# LoRa_Photon2.net
KiCad netlist of a schematic drawn in EAGLE
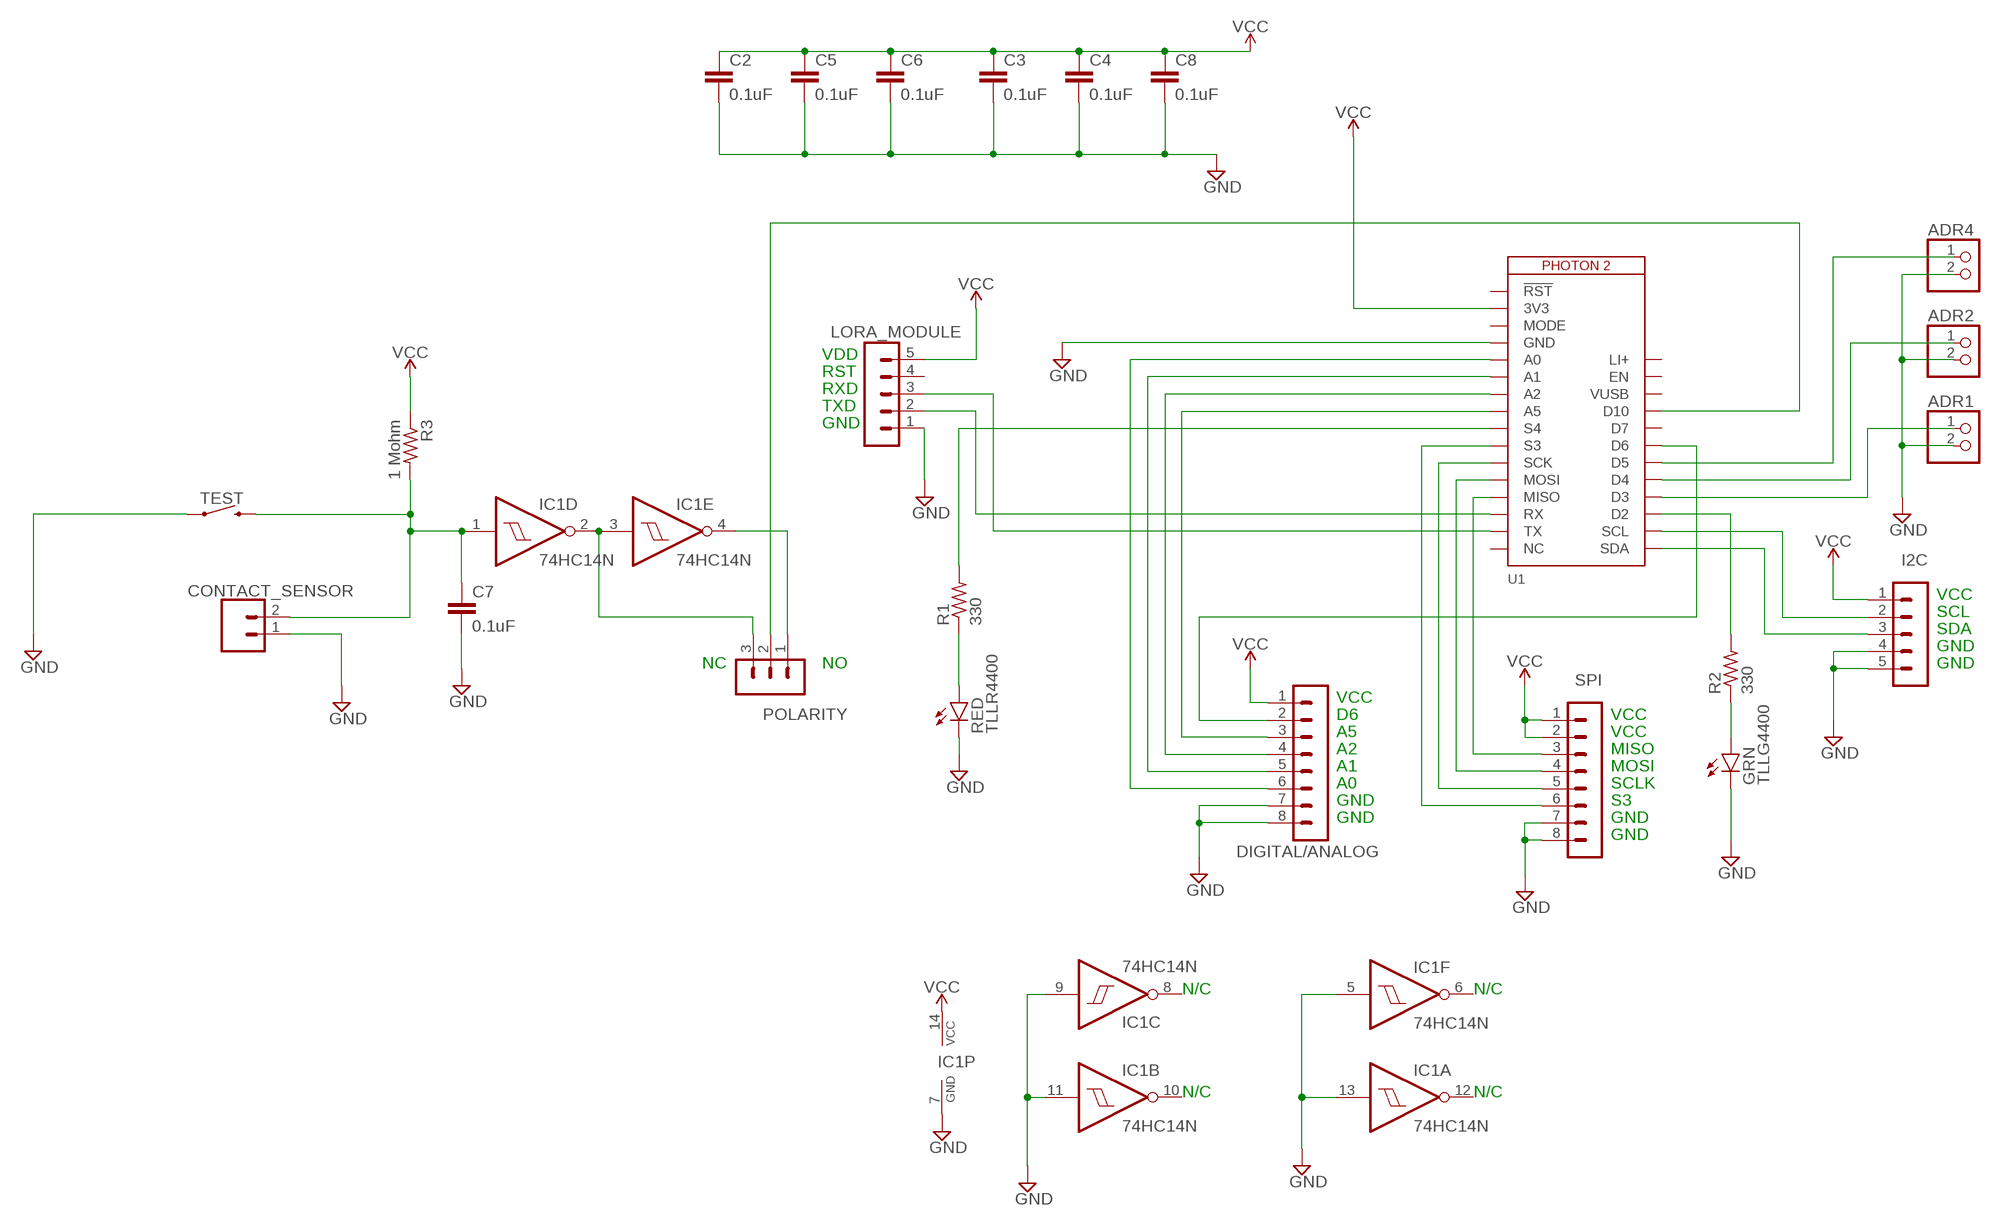
[diagram p0: schematic, sheet 2]

(export (version "E")
  (design (tool "Eeschema 10.0.6"))
  (components
    (comp (ref "ADR1")
      (value "PINHD-1X2")
      (footprint "eagle-import:1X02")
      (libsource (lib "eagle-import") (part "PINHD-1X2"))
    )
    (comp (ref "ADR2")
      (value "PINHD-1X2")
      (footprint "eagle-import:1X02")
      (libsource (lib "eagle-import") (part "PINHD-1X2"))
    )
    (comp (ref "ADR4")
      (value "PINHD-1X2")
      (footprint "eagle-import:1X02")
      (libsource (lib "eagle-import") (part "PINHD-1X2"))
    )
    (comp (ref "C2")
      (value "0.1uF")
      (footprint "eagle-import:CAP-PTH-SMALL-KIT")
      (libsource (lib "eagle-import") (part "0.1UF-KIT-EZ-50V-20%"))
    )
    (comp (ref "C3")
      (value "0.1uF")
      (footprint "eagle-import:CAP-PTH-SMALL-KIT")
      (libsource (lib "eagle-import") (part "0.1UF-KIT-EZ-50V-20%"))
    )
    (comp (ref "C4")
      (value "0.1uF")
      (footprint "eagle-import:CAP-PTH-SMALL-KIT")
      (libsource (lib "eagle-import") (part "0.1UF-KIT-EZ-50V-20%"))
    )
    (comp (ref "C5")
      (value "0.1uF")
      (footprint "eagle-import:CAP-PTH-SMALL-KIT")
      (libsource (lib "eagle-import") (part "0.1UF-KIT-EZ-50V-20%"))
    )
    (comp (ref "C6")
      (value "0.1uF")
      (footprint "eagle-import:CAP-PTH-SMALL-KIT")
      (libsource (lib "eagle-import") (part "0.1UF-KIT-EZ-50V-20%"))
    )
    (comp (ref "C7")
      (value "0.1uF")
      (footprint "eagle-import:CAP-PTH-SMALL-KIT")
      (libsource (lib "eagle-import") (part "0.1UF-KIT-EZ-50V-20%"))
    )
    (comp (ref "C8")
      (value "0.1uF")
      (footprint "eagle-import:CAP-PTH-SMALL-KIT")
      (libsource (lib "eagle-import") (part "0.1UF-KIT-EZ-50V-20%"))
    )
    (comp (ref "CONTACT_SENSOR")
      (value "CONN_023.5MM")
      (footprint "eagle-import:SCREWTERMINAL-3.5MM-2")
      (libsource (lib "eagle-import") (part "CONN_023.5MM"))
    )
    (comp (ref "DIGITAL/ANALOG")
      (value "MA08-1")
      (footprint "eagle-import:MA08-1")
      (libsource (lib "eagle-import") (part "MA08-1"))
    )
    (comp (ref "GRN")
      (value "TLLG4400")
      (footprint "eagle-import:LED3MM")
      (fields (field (name "MF") "VISHAY SEMICONDUCTOR"))
      (libsource (lib "eagle-import") (part "TLLG4400"))
    )
    (comp (ref "I2C")
      (value "MA05-1")
      (footprint "eagle-import:MA05-1")
      (libsource (lib "eagle-import") (part "MA05-1"))
    )
    (comp (ref "IC1")
      (value "74HC14N")
      (footprint "eagle-import:DIL14")
      (libsource (lib "eagle-import") (part "7414NHC"))
    )
    (comp (ref "LORA_MODULE")
      (value "MA05-1")
      (footprint "eagle-import:MA05-1")
      (libsource (lib "eagle-import") (part "MA05-1"))
    )
    (comp (ref "POLARITY")
      (value "MA03-1")
      (footprint "eagle-import:MA03-1")
      (libsource (lib "eagle-import") (part "MA03-1"))
    )
    (comp (ref "R1")
      (value "330")
      (footprint "eagle-import:0309_12")
      (libsource (lib "eagle-import") (part "R-US_0309/12"))
    )
    (comp (ref "R2")
      (value "330")
      (footprint "eagle-import:0309_12")
      (libsource (lib "eagle-import") (part "R-US_0309/12"))
    )
    (comp (ref "R3")
      (value "1 Mohm")
      (footprint "eagle-import:0309_12")
      (libsource (lib "eagle-import") (part "R-US_0309/12"))
    )
    (comp (ref "RED")
      (value "TLLR4400")
      (footprint "eagle-import:LED3MM")
      (fields (field (name "MF") "VISHAY SEMICONDUCTOR"))
      (libsource (lib "eagle-import") (part "TLLR4400"))
    )
    (comp (ref "SPI")
      (value "MA08-1")
      (footprint "eagle-import:MA08-1")
      (libsource (lib "eagle-import") (part "MA08-1"))
    )
    (comp (ref "TEST")
      (value "MOMENTARY-SWITCH-SPST-PTH-6.0MM")
      (footprint "eagle-import:TACTILE_SWITCH_PTH_6.0MM")
      (libsource (lib "eagle-import") (part "MOMENTARY-SWITCH-SPST-PTH-6.0MM"))
    )
    (comp (ref "U1")
      (value "PHOTON2")
      (footprint "eagle-import:PHOTON2")
      (libsource (lib "eagle-import") (part "PHOTON2"))
    )
  )
  (nets
    (net (code "1") (name "GND") (class "Default")
      (node (ref "ADR1") (pin "2") (pinfunction "2_2") (pintype "passive"))
      (node (ref "ADR2") (pin "2") (pinfunction "2_2") (pintype "passive"))
      (node (ref "ADR4") (pin "2") (pinfunction "2_2") (pintype "passive"))
      (node (ref "C2") (pin "2") (pinfunction "2_2") (pintype "passive"))
      (node (ref "C3") (pin "2") (pinfunction "2_2") (pintype "passive"))
      (node (ref "C4") (pin "2") (pinfunction "2_2") (pintype "passive"))
      (node (ref "C5") (pin "2") (pinfunction "2_2") (pintype "passive"))
      (node (ref "C6") (pin "2") (pinfunction "2_2") (pintype "passive"))
      (node (ref "C7") (pin "2") (pinfunction "2_2") (pintype "passive"))
      (node (ref "C8") (pin "2") (pinfunction "2_2") (pintype "passive"))
      (node (ref "CONTACT_SENSOR") (pin "1") (pinfunction "1_1") (pintype "passive"))
      (node (ref "DIGITAL/ANALOG") (pin "7") (pinfunction "7_7") (pintype "passive"))
      (node (ref "DIGITAL/ANALOG") (pin "8") (pinfunction "8_8") (pintype "passive"))
      (node (ref "GRN") (pin "K") (pinfunction "C_K") (pintype "passive"))
      (node (ref "I2C") (pin "4") (pinfunction "4_4") (pintype "passive"))
      (node (ref "I2C") (pin "5") (pinfunction "5_5") (pintype "passive"))
      (node (ref "IC1") (pin "11") (pinfunction "I_11") (pintype "input"))
      (node (ref "IC1") (pin "13") (pinfunction "I_13") (pintype "input"))
      (node (ref "IC1") (pin "5") (pinfunction "I_5") (pintype "input"))
      (node (ref "IC1") (pin "7") (pinfunction "GND_7") (pintype "power_in"))
      (node (ref "IC1") (pin "9") (pinfunction "I_9") (pintype "input"))
      (node (ref "LORA_MODULE") (pin "1") (pinfunction "1_1") (pintype "passive"))
      (node (ref "RED") (pin "K") (pinfunction "C_K") (pintype "passive"))
      (node (ref "SPI") (pin "7") (pinfunction "7_7") (pintype "passive"))
      (node (ref "SPI") (pin "8") (pinfunction "8_8") (pintype "passive"))
      (node (ref "TEST") (pin "1") (pinfunction "1_1") (pintype "passive"))
      (node (ref "U1") (pin "4") (pinfunction "GND_4") (pintype "power_in"))
    )
    (net (code "2") (name "LI+") (class "Default")
      (node (ref "U1") (pin "28") (pinfunction "LI+_28") (pintype "power_in"))
    )
    (net (code "3") (name "Net-(GRN-PadA)") (class "Default")
      (node (ref "GRN") (pin "A") (pinfunction "A_A") (pintype "passive"))
      (node (ref "R2") (pin "1") (pinfunction "1_1") (pintype "passive"))
    )
    (net (code "4") (name "Net-(IC1D-I)") (class "Default")
      (node (ref "C7") (pin "1") (pinfunction "1_1") (pintype "passive"))
      (node (ref "CONTACT_SENSOR") (pin "2") (pinfunction "2_2") (pintype "passive"))
      (node (ref "IC1") (pin "1") (pinfunction "I_1") (pintype "input"))
      (node (ref "R3") (pin "2") (pinfunction "2_2") (pintype "passive"))
      (node (ref "TEST") (pin "3") (pinfunction "2_3") (pintype "passive"))
    )
    (net (code "5") (name "Net-(IC1D-O)") (class "Default")
      (node (ref "IC1") (pin "2") (pinfunction "O_2") (pintype "output"))
      (node (ref "IC1") (pin "3") (pinfunction "I_3") (pintype "input"))
      (node (ref "POLARITY") (pin "3") (pinfunction "3_3") (pintype "passive"))
    )
    (net (code "6") (name "Net-(IC1E-O)") (class "Default")
      (node (ref "IC1") (pin "4") (pinfunction "O_4") (pintype "output"))
      (node (ref "POLARITY") (pin "1") (pinfunction "1_1") (pintype "passive"))
    )
    (net (code "7") (name "Net-(R1-Pad1)") (class "Default")
      (node (ref "R1") (pin "1") (pinfunction "1_1") (pintype "passive"))
      (node (ref "RED") (pin "A") (pinfunction "A_A") (pintype "passive"))
    )
    (net (code "8") (name "Net-(U1-A0)") (class "Default")
      (node (ref "DIGITAL/ANALOG") (pin "6") (pinfunction "6_6") (pintype "passive"))
      (node (ref "U1") (pin "5") (pinfunction "A0_5") (pintype "bidirectional"))
    )
    (net (code "9") (name "Net-(U1-A1)") (class "Default")
      (node (ref "DIGITAL/ANALOG") (pin "5") (pinfunction "5_5") (pintype "passive"))
      (node (ref "U1") (pin "6") (pinfunction "A1_6") (pintype "bidirectional"))
    )
    (net (code "10") (name "Net-(U1-A2)") (class "Default")
      (node (ref "DIGITAL/ANALOG") (pin "4") (pinfunction "4_4") (pintype "passive"))
      (node (ref "U1") (pin "7") (pinfunction "A2_7") (pintype "bidirectional"))
    )
    (net (code "11") (name "Net-(U1-A5)") (class "Default")
      (node (ref "DIGITAL/ANALOG") (pin "3") (pinfunction "3_3") (pintype "passive"))
      (node (ref "U1") (pin "8") (pinfunction "A5_8") (pintype "bidirectional"))
    )
    (net (code "12") (name "Net-(U1-D2)") (class "Default")
      (node (ref "R2") (pin "2") (pinfunction "2_2") (pintype "passive"))
      (node (ref "U1") (pin "19") (pinfunction "D2_19") (pintype "bidirectional"))
    )
    (net (code "13") (name "Net-(U1-D3)") (class "Default")
      (node (ref "ADR1") (pin "1") (pinfunction "1_1") (pintype "passive"))
      (node (ref "U1") (pin "20") (pinfunction "D3_20") (pintype "bidirectional"))
    )
    (net (code "14") (name "Net-(U1-D4)") (class "Default")
      (node (ref "ADR2") (pin "1") (pinfunction "1_1") (pintype "passive"))
      (node (ref "U1") (pin "21") (pinfunction "D4_21") (pintype "bidirectional"))
    )
    (net (code "15") (name "Net-(U1-D5)") (class "Default")
      (node (ref "ADR4") (pin "1") (pinfunction "1_1") (pintype "passive"))
      (node (ref "U1") (pin "22") (pinfunction "D5_22") (pintype "bidirectional"))
    )
    (net (code "16") (name "Net-(U1-D6)") (class "Default")
      (node (ref "DIGITAL/ANALOG") (pin "2") (pinfunction "2_2") (pintype "passive"))
      (node (ref "U1") (pin "23") (pinfunction "D6_23") (pintype "bidirectional"))
    )
    (net (code "17") (name "Net-(U1-D10)") (class "Default")
      (node (ref "POLARITY") (pin "2") (pinfunction "2_2") (pintype "passive"))
      (node (ref "U1") (pin "25") (pinfunction "D10_25") (pintype "bidirectional"))
    )
    (net (code "18") (name "Net-(U1-MISO)") (class "Default")
      (node (ref "SPI") (pin "3") (pinfunction "3_3") (pintype "passive"))
      (node (ref "U1") (pin "13") (pinfunction "MISO_13") (pintype "bidirectional"))
    )
    (net (code "19") (name "Net-(U1-MOSI)") (class "Default")
      (node (ref "SPI") (pin "4") (pinfunction "4_4") (pintype "passive"))
      (node (ref "U1") (pin "12") (pinfunction "MOSI_12") (pintype "bidirectional"))
    )
    (net (code "20") (name "Net-(U1-RX)") (class "Default")
      (node (ref "LORA_MODULE") (pin "2") (pinfunction "2_2") (pintype "passive"))
      (node (ref "U1") (pin "14") (pinfunction "RX_14") (pintype "bidirectional"))
    )
    (net (code "21") (name "Net-(U1-S3)") (class "Default")
      (node (ref "SPI") (pin "6") (pinfunction "6_6") (pintype "passive"))
      (node (ref "U1") (pin "10") (pinfunction "S3_10") (pintype "bidirectional"))
    )
    (net (code "22") (name "Net-(U1-S4)") (class "Default")
      (node (ref "R1") (pin "2") (pinfunction "2_2") (pintype "passive"))
      (node (ref "U1") (pin "9") (pinfunction "S4_9") (pintype "bidirectional"))
    )
    (net (code "23") (name "Net-(U1-SCK)") (class "Default")
      (node (ref "SPI") (pin "5") (pinfunction "5_5") (pintype "passive"))
      (node (ref "U1") (pin "11") (pinfunction "SCK_11") (pintype "bidirectional"))
    )
    (net (code "24") (name "Net-(U1-SCL)") (class "Default")
      (node (ref "I2C") (pin "2") (pinfunction "2_2") (pintype "passive"))
      (node (ref "U1") (pin "18") (pinfunction "SCL_18") (pintype "bidirectional"))
    )
    (net (code "25") (name "Net-(U1-SDA)") (class "Default")
      (node (ref "I2C") (pin "3") (pinfunction "3_3") (pintype "passive"))
      (node (ref "U1") (pin "17") (pinfunction "SDA_17") (pintype "bidirectional"))
    )
    (net (code "26") (name "Net-(U1-TX)") (class "Default")
      (node (ref "LORA_MODULE") (pin "3") (pinfunction "3_3") (pintype "passive"))
      (node (ref "U1") (pin "15") (pinfunction "TX_15") (pintype "bidirectional"))
    )
    (net (code "27") (name "VCC") (class "Default")
      (node (ref "C2") (pin "1") (pinfunction "1_1") (pintype "passive"))
      (node (ref "C3") (pin "1") (pinfunction "1_1") (pintype "passive"))
      (node (ref "C4") (pin "1") (pinfunction "1_1") (pintype "passive"))
      (node (ref "C5") (pin "1") (pinfunction "1_1") (pintype "passive"))
      (node (ref "C6") (pin "1") (pinfunction "1_1") (pintype "passive"))
      (node (ref "C8") (pin "1") (pinfunction "1_1") (pintype "passive"))
      (node (ref "DIGITAL/ANALOG") (pin "1") (pinfunction "1_1") (pintype "passive"))
      (node (ref "I2C") (pin "1") (pinfunction "1_1") (pintype "passive"))
      (node (ref "IC1") (pin "14") (pinfunction "VCC_14") (pintype "power_in"))
      (node (ref "LORA_MODULE") (pin "5") (pinfunction "5_5") (pintype "passive"))
      (node (ref "R3") (pin "1") (pinfunction "1_1") (pintype "passive"))
      (node (ref "SPI") (pin "1") (pinfunction "1_1") (pintype "passive"))
      (node (ref "SPI") (pin "2") (pinfunction "2_2") (pintype "passive"))
      (node (ref "U1") (pin "2") (pinfunction "3V3_2") (pintype "power_in"))
    )
    (net (code "28") (name "VUSB") (class "Default")
      (node (ref "U1") (pin "26") (pinfunction "VUSB_26") (pintype "power_in"))
    )
    (net (code "29") (name "unconnected-(IC1A-O-Pad12)") (class "Default")
      (node (ref "IC1") (pin "12") (pinfunction "O_12") (pintype "output"))
    )
    (net (code "30") (name "unconnected-(IC1B-O-Pad10)") (class "Default")
      (node (ref "IC1") (pin "10") (pinfunction "O_10") (pintype "output"))
    )
    (net (code "31") (name "unconnected-(IC1C-O-Pad8)") (class "Default")
      (node (ref "IC1") (pin "8") (pinfunction "O_8") (pintype "output"))
    )
    (net (code "32") (name "unconnected-(IC1F-O-Pad6)") (class "Default")
      (node (ref "IC1") (pin "6") (pinfunction "O_6") (pintype "output"))
    )
    (net (code "33") (name "unconnected-(LORA_MODULE-Pad4)") (class "Default")
      (node (ref "LORA_MODULE") (pin "4") (pinfunction "4_4") (pintype "passive"))
    )
    (net (code "34") (name "unconnected-(U1-D7-Pad24)") (class "Default")
      (node (ref "U1") (pin "24") (pinfunction "D7_24") (pintype "bidirectional"))
    )
    (net (code "35") (name "unconnected-(U1-EN-Pad27)") (class "Default")
      (node (ref "U1") (pin "27") (pinfunction "EN_27") (pintype "input"))
    )
    (net (code "36") (name "unconnected-(U1-MODE-Pad3)") (class "Default")
      (node (ref "U1") (pin "3") (pinfunction "MODE_3") (pintype "bidirectional"))
    )
    (net (code "37") (name "unconnected-(U1-NC-Pad16)") (class "Default")
      (node (ref "U1") (pin "16") (pinfunction "NC_16") (pintype "bidirectional"))
    )
    (net (code "38") (name "unconnected-(U1-~{RST}-Pad1)") (class "Default")
      (node (ref "U1") (pin "1") (pinfunction "~{RST}_1") (pintype "input"))
    )
  )
)
